# con-right.net
KiCad netlist of a schematic drawn in Altium Designer
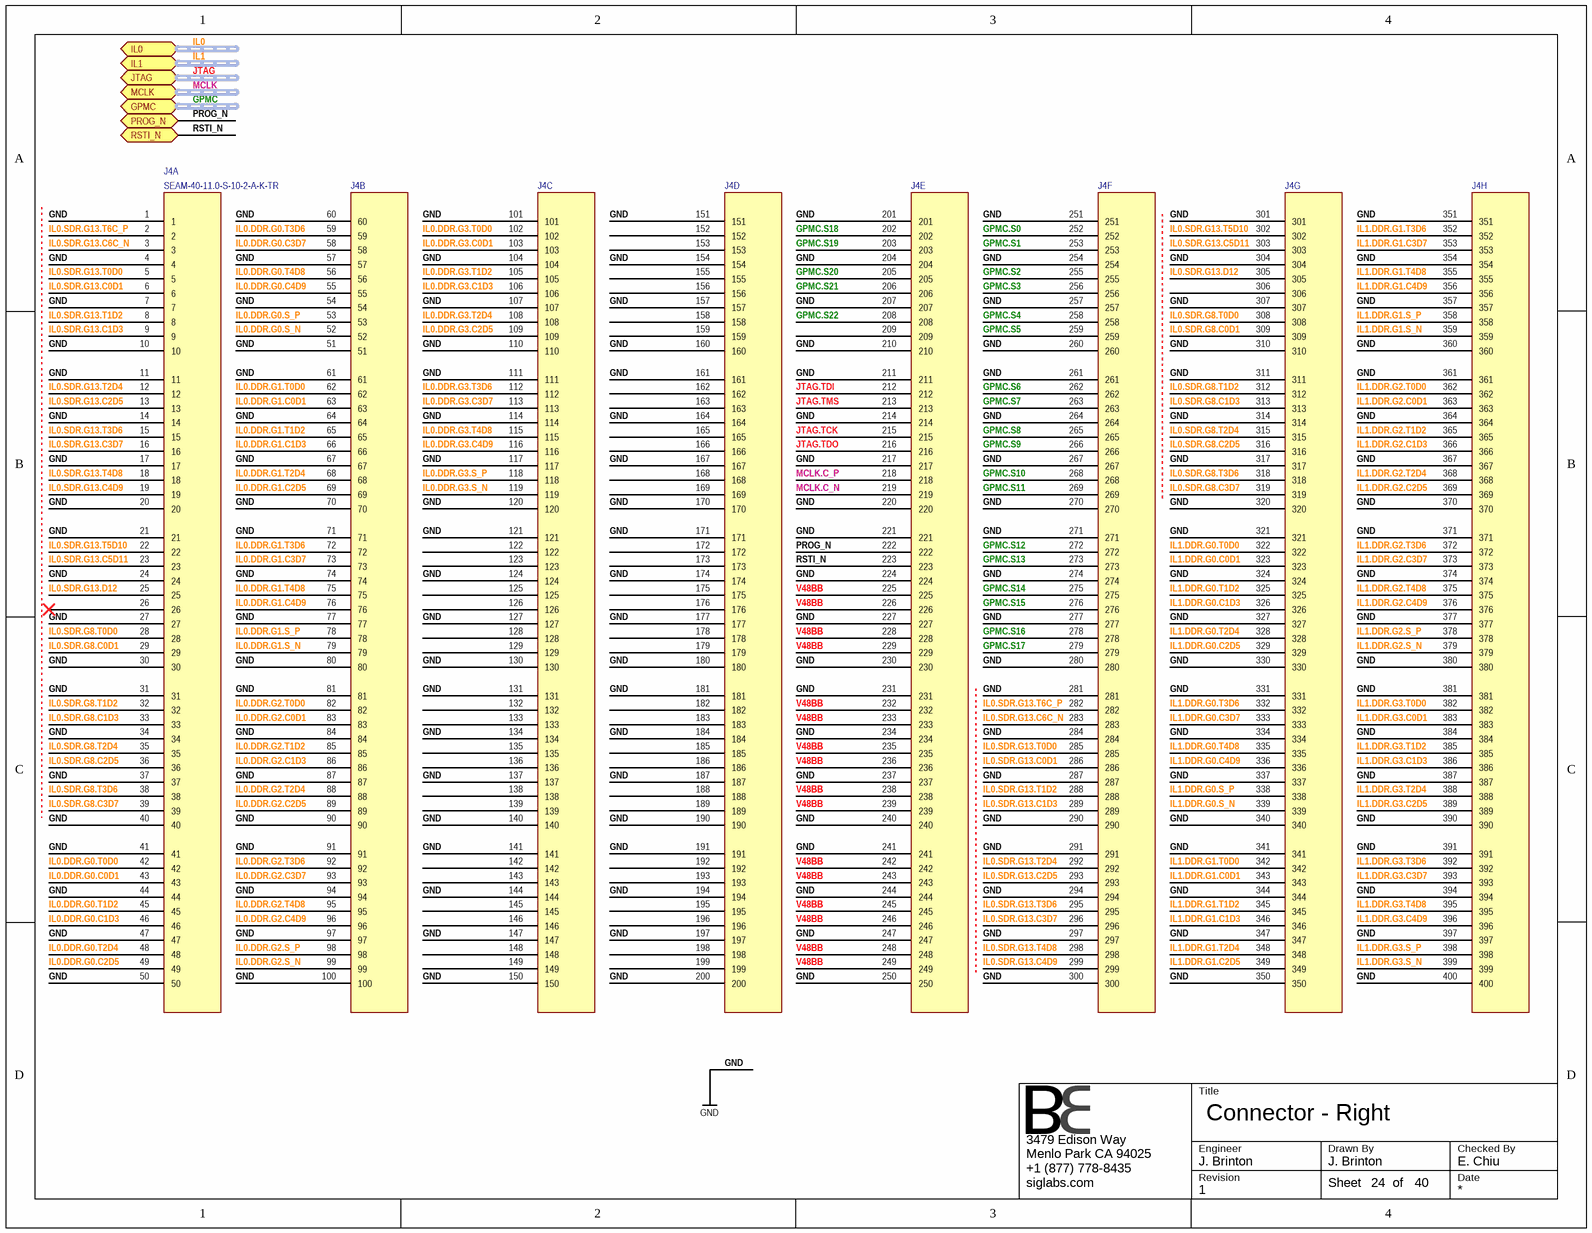
[diagram p0: con-right.SchDoc]

(export (version "E")
  (design (tool "Eeschema 10.0.6"))
  (components
    (comp (ref "J4")
      (value "SEAM-40-11.0-S-10-2-A-K-TR")
      (footprint "samtec:SEAM-40-11.0-S-10-2-A-K-TR")
      (description "Terminal Array Assembly, Surface Mount, 0.050\" Pitch, 400 Pins")
      (fields (field (name "MANUFACTURER") "Samtec"))
      (libsource (lib "samtec") (part "SEAM-40-11.0-S-10-2-A-K-TR"))
    )
  )
  (nets
    (net (code "6") (name "/GPMC.S0") (class "Default")
      (node (ref "J4") (pin "252") (pinfunction "252_252") (pintype "passive"))
    )
    (net (code "7") (name "/GPMC.S1") (class "Default")
      (node (ref "J4") (pin "253") (pinfunction "253_253") (pintype "passive"))
    )
    (net (code "8") (name "/GPMC.S2") (class "Default")
      (node (ref "J4") (pin "255") (pinfunction "255_255") (pintype "passive"))
    )
    (net (code "9") (name "/GPMC.S3") (class "Default")
      (node (ref "J4") (pin "256") (pinfunction "256_256") (pintype "passive"))
    )
    (net (code "10") (name "/GPMC.S4") (class "Default")
      (node (ref "J4") (pin "258") (pinfunction "258_258") (pintype "passive"))
    )
    (net (code "11") (name "/GPMC.S5") (class "Default")
      (node (ref "J4") (pin "259") (pinfunction "259_259") (pintype "passive"))
    )
    (net (code "12") (name "/GPMC.S6") (class "Default")
      (node (ref "J4") (pin "262") (pinfunction "262_262") (pintype "passive"))
    )
    (net (code "13") (name "/GPMC.S7") (class "Default")
      (node (ref "J4") (pin "263") (pinfunction "263_263") (pintype "passive"))
    )
    (net (code "14") (name "/GPMC.S8") (class "Default")
      (node (ref "J4") (pin "265") (pinfunction "265_265") (pintype "passive"))
    )
    (net (code "15") (name "/GPMC.S9") (class "Default")
      (node (ref "J4") (pin "266") (pinfunction "266_266") (pintype "passive"))
    )
    (net (code "16") (name "/GPMC.S10") (class "Default")
      (node (ref "J4") (pin "268") (pinfunction "268_268") (pintype "passive"))
    )
    (net (code "17") (name "/GPMC.S11") (class "Default")
      (node (ref "J4") (pin "269") (pinfunction "269_269") (pintype "passive"))
    )
    (net (code "18") (name "/GPMC.S12") (class "Default")
      (node (ref "J4") (pin "272") (pinfunction "272_272") (pintype "passive"))
    )
    (net (code "19") (name "/GPMC.S13") (class "Default")
      (node (ref "J4") (pin "273") (pinfunction "273_273") (pintype "passive"))
    )
    (net (code "20") (name "/GPMC.S14") (class "Default")
      (node (ref "J4") (pin "275") (pinfunction "275_275") (pintype "passive"))
    )
    (net (code "21") (name "/GPMC.S15") (class "Default")
      (node (ref "J4") (pin "276") (pinfunction "276_276") (pintype "passive"))
    )
    (net (code "22") (name "/GPMC.S16") (class "Default")
      (node (ref "J4") (pin "278") (pinfunction "278_278") (pintype "passive"))
    )
    (net (code "23") (name "/GPMC.S17") (class "Default")
      (node (ref "J4") (pin "279") (pinfunction "279_279") (pintype "passive"))
    )
    (net (code "24") (name "/GPMC.S18") (class "Default")
      (node (ref "J4") (pin "202") (pinfunction "202_202") (pintype "passive"))
    )
    (net (code "25") (name "/GPMC.S19") (class "Default")
      (node (ref "J4") (pin "203") (pinfunction "203_203") (pintype "passive"))
    )
    (net (code "26") (name "/GPMC.S20") (class "Default")
      (node (ref "J4") (pin "205") (pinfunction "205_205") (pintype "passive"))
    )
    (net (code "27") (name "/GPMC.S21") (class "Default")
      (node (ref "J4") (pin "206") (pinfunction "206_206") (pintype "passive"))
    )
    (net (code "28") (name "/GPMC.S22") (class "Default")
      (node (ref "J4") (pin "208") (pinfunction "208_208") (pintype "passive"))
    )
    (net (code "29") (name "/IL0.DDR.G0.C0D1") (class "Default")
      (node (ref "J4") (pin "43") (pinfunction "43_43") (pintype "passive"))
    )
    (net (code "30") (name "/IL0.DDR.G0.C1D3") (class "Default")
      (node (ref "J4") (pin "46") (pinfunction "46_46") (pintype "passive"))
    )
    (net (code "31") (name "/IL0.DDR.G0.C2D5") (class "Default")
      (node (ref "J4") (pin "49") (pinfunction "49_49") (pintype "passive"))
    )
    (net (code "32") (name "/IL0.DDR.G0.C3D7") (class "Default")
      (node (ref "J4") (pin "58") (pinfunction "58_58") (pintype "passive"))
    )
    (net (code "33") (name "/IL0.DDR.G0.C4D9") (class "Default")
      (node (ref "J4") (pin "55") (pinfunction "55_55") (pintype "passive"))
    )
    (net (code "34") (name "/IL0.DDR.G0.S_N") (class "Default")
      (node (ref "J4") (pin "52") (pinfunction "52_52") (pintype "passive"))
    )
    (net (code "35") (name "/IL0.DDR.G0.S_P") (class "Default")
      (node (ref "J4") (pin "53") (pinfunction "53_53") (pintype "passive"))
    )
    (net (code "36") (name "/IL0.DDR.G0.T0D0") (class "Default")
      (node (ref "J4") (pin "42") (pinfunction "42_42") (pintype "passive"))
    )
    (net (code "37") (name "/IL0.DDR.G0.T1D2") (class "Default")
      (node (ref "J4") (pin "45") (pinfunction "45_45") (pintype "passive"))
    )
    (net (code "38") (name "/IL0.DDR.G0.T2D4") (class "Default")
      (node (ref "J4") (pin "48") (pinfunction "48_48") (pintype "passive"))
    )
    (net (code "39") (name "/IL0.DDR.G0.T3D6") (class "Default")
      (node (ref "J4") (pin "59") (pinfunction "59_59") (pintype "passive"))
    )
    (net (code "40") (name "/IL0.DDR.G0.T4D8") (class "Default")
      (node (ref "J4") (pin "56") (pinfunction "56_56") (pintype "passive"))
    )
    (net (code "41") (name "/IL0.DDR.G1.C0D1") (class "Default")
      (node (ref "J4") (pin "63") (pinfunction "63_63") (pintype "passive"))
    )
    (net (code "42") (name "/IL0.DDR.G1.C1D3") (class "Default")
      (node (ref "J4") (pin "66") (pinfunction "66_66") (pintype "passive"))
    )
    (net (code "43") (name "/IL0.DDR.G1.C2D5") (class "Default")
      (node (ref "J4") (pin "69") (pinfunction "69_69") (pintype "passive"))
    )
    (net (code "44") (name "/IL0.DDR.G1.C3D7") (class "Default")
      (node (ref "J4") (pin "73") (pinfunction "73_73") (pintype "passive"))
    )
    (net (code "45") (name "/IL0.DDR.G1.C4D9") (class "Default")
      (node (ref "J4") (pin "76") (pinfunction "76_76") (pintype "passive"))
    )
    (net (code "46") (name "/IL0.DDR.G1.S_N") (class "Default")
      (node (ref "J4") (pin "79") (pinfunction "79_79") (pintype "passive"))
    )
    (net (code "47") (name "/IL0.DDR.G1.S_P") (class "Default")
      (node (ref "J4") (pin "78") (pinfunction "78_78") (pintype "passive"))
    )
    (net (code "48") (name "/IL0.DDR.G1.T0D0") (class "Default")
      (node (ref "J4") (pin "62") (pinfunction "62_62") (pintype "passive"))
    )
    (net (code "49") (name "/IL0.DDR.G1.T1D2") (class "Default")
      (node (ref "J4") (pin "65") (pinfunction "65_65") (pintype "passive"))
    )
    (net (code "50") (name "/IL0.DDR.G1.T2D4") (class "Default")
      (node (ref "J4") (pin "68") (pinfunction "68_68") (pintype "passive"))
    )
    (net (code "51") (name "/IL0.DDR.G1.T3D6") (class "Default")
      (node (ref "J4") (pin "72") (pinfunction "72_72") (pintype "passive"))
    )
    (net (code "52") (name "/IL0.DDR.G1.T4D8") (class "Default")
      (node (ref "J4") (pin "75") (pinfunction "75_75") (pintype "passive"))
    )
    (net (code "53") (name "/IL0.DDR.G2.C0D1") (class "Default")
      (node (ref "J4") (pin "83") (pinfunction "83_83") (pintype "passive"))
    )
    (net (code "54") (name "/IL0.DDR.G2.C1D3") (class "Default")
      (node (ref "J4") (pin "86") (pinfunction "86_86") (pintype "passive"))
    )
    (net (code "55") (name "/IL0.DDR.G2.C2D5") (class "Default")
      (node (ref "J4") (pin "89") (pinfunction "89_89") (pintype "passive"))
    )
    (net (code "56") (name "/IL0.DDR.G2.C3D7") (class "Default")
      (node (ref "J4") (pin "93") (pinfunction "93_93") (pintype "passive"))
    )
    (net (code "57") (name "/IL0.DDR.G2.C4D9") (class "Default")
      (node (ref "J4") (pin "96") (pinfunction "96_96") (pintype "passive"))
    )
    (net (code "58") (name "/IL0.DDR.G2.S_N") (class "Default")
      (node (ref "J4") (pin "99") (pinfunction "99_99") (pintype "passive"))
    )
    (net (code "59") (name "/IL0.DDR.G2.S_P") (class "Default")
      (node (ref "J4") (pin "98") (pinfunction "98_98") (pintype "passive"))
    )
    (net (code "60") (name "/IL0.DDR.G2.T0D0") (class "Default")
      (node (ref "J4") (pin "82") (pinfunction "82_82") (pintype "passive"))
    )
    (net (code "61") (name "/IL0.DDR.G2.T1D2") (class "Default")
      (node (ref "J4") (pin "85") (pinfunction "85_85") (pintype "passive"))
    )
    (net (code "62") (name "/IL0.DDR.G2.T2D4") (class "Default")
      (node (ref "J4") (pin "88") (pinfunction "88_88") (pintype "passive"))
    )
    (net (code "63") (name "/IL0.DDR.G2.T3D6") (class "Default")
      (node (ref "J4") (pin "92") (pinfunction "92_92") (pintype "passive"))
    )
    (net (code "64") (name "/IL0.DDR.G2.T4D8") (class "Default")
      (node (ref "J4") (pin "95") (pinfunction "95_95") (pintype "passive"))
    )
    (net (code "65") (name "/IL0.DDR.G3.C0D1") (class "Default")
      (node (ref "J4") (pin "103") (pinfunction "103_103") (pintype "passive"))
    )
    (net (code "66") (name "/IL0.DDR.G3.C1D3") (class "Default")
      (node (ref "J4") (pin "106") (pinfunction "106_106") (pintype "passive"))
    )
    (net (code "67") (name "/IL0.DDR.G3.C2D5") (class "Default")
      (node (ref "J4") (pin "109") (pinfunction "109_109") (pintype "passive"))
    )
    (net (code "68") (name "/IL0.DDR.G3.C3D7") (class "Default")
      (node (ref "J4") (pin "113") (pinfunction "113_113") (pintype "passive"))
    )
    (net (code "69") (name "/IL0.DDR.G3.C4D9") (class "Default")
      (node (ref "J4") (pin "116") (pinfunction "116_116") (pintype "passive"))
    )
    (net (code "70") (name "/IL0.DDR.G3.S_N") (class "Default")
      (node (ref "J4") (pin "119") (pinfunction "119_119") (pintype "passive"))
    )
    (net (code "71") (name "/IL0.DDR.G3.S_P") (class "Default")
      (node (ref "J4") (pin "118") (pinfunction "118_118") (pintype "passive"))
    )
    (net (code "72") (name "/IL0.DDR.G3.T0D0") (class "Default")
      (node (ref "J4") (pin "102") (pinfunction "102_102") (pintype "passive"))
    )
    (net (code "73") (name "/IL0.DDR.G3.T1D2") (class "Default")
      (node (ref "J4") (pin "105") (pinfunction "105_105") (pintype "passive"))
    )
    (net (code "74") (name "/IL0.DDR.G3.T2D4") (class "Default")
      (node (ref "J4") (pin "108") (pinfunction "108_108") (pintype "passive"))
    )
    (net (code "75") (name "/IL0.DDR.G3.T3D6") (class "Default")
      (node (ref "J4") (pin "112") (pinfunction "112_112") (pintype "passive"))
    )
    (net (code "76") (name "/IL0.DDR.G3.T4D8") (class "Default")
      (node (ref "J4") (pin "115") (pinfunction "115_115") (pintype "passive"))
    )
    (net (code "77") (name "/IL0.SDR.G8.C0D1") (class "Default")
      (node (ref "J4") (pin "29") (pinfunction "29_29") (pintype "passive"))
      (node (ref "J4") (pin "309") (pinfunction "309_309") (pintype "passive"))
    )
    (net (code "78") (name "/IL0.SDR.G8.C1D3") (class "Default")
      (node (ref "J4") (pin "313") (pinfunction "313_313") (pintype "passive"))
      (node (ref "J4") (pin "33") (pinfunction "33_33") (pintype "passive"))
    )
    (net (code "79") (name "/IL0.SDR.G8.C2D5") (class "Default")
      (node (ref "J4") (pin "316") (pinfunction "316_316") (pintype "passive"))
      (node (ref "J4") (pin "36") (pinfunction "36_36") (pintype "passive"))
    )
    (net (code "80") (name "/IL0.SDR.G8.C3D7") (class "Default")
      (node (ref "J4") (pin "319") (pinfunction "319_319") (pintype "passive"))
      (node (ref "J4") (pin "39") (pinfunction "39_39") (pintype "passive"))
    )
    (net (code "81") (name "/IL0.SDR.G8.T0D0") (class "Default")
      (node (ref "J4") (pin "28") (pinfunction "28_28") (pintype "passive"))
      (node (ref "J4") (pin "308") (pinfunction "308_308") (pintype "passive"))
    )
    (net (code "82") (name "/IL0.SDR.G8.T1D2") (class "Default")
      (node (ref "J4") (pin "312") (pinfunction "312_312") (pintype "passive"))
      (node (ref "J4") (pin "32") (pinfunction "32_32") (pintype "passive"))
    )
    (net (code "83") (name "/IL0.SDR.G8.T2D4") (class "Default")
      (node (ref "J4") (pin "315") (pinfunction "315_315") (pintype "passive"))
      (node (ref "J4") (pin "35") (pinfunction "35_35") (pintype "passive"))
    )
    (net (code "84") (name "/IL0.SDR.G8.T3D6") (class "Default")
      (node (ref "J4") (pin "318") (pinfunction "318_318") (pintype "passive"))
      (node (ref "J4") (pin "38") (pinfunction "38_38") (pintype "passive"))
    )
    (net (code "85") (name "/IL0.SDR.G13.C0D1") (class "Default")
      (node (ref "J4") (pin "286") (pinfunction "286_286") (pintype "passive"))
      (node (ref "J4") (pin "6") (pinfunction "6_6") (pintype "passive"))
    )
    (net (code "86") (name "/IL0.SDR.G13.C1D3") (class "Default")
      (node (ref "J4") (pin "289") (pinfunction "289_289") (pintype "passive"))
      (node (ref "J4") (pin "9") (pinfunction "9_9") (pintype "passive"))
    )
    (net (code "87") (name "/IL0.SDR.G13.C2D5") (class "Default")
      (node (ref "J4") (pin "13") (pinfunction "13_13") (pintype "passive"))
      (node (ref "J4") (pin "293") (pinfunction "293_293") (pintype "passive"))
    )
    (net (code "88") (name "/IL0.SDR.G13.C3D7") (class "Default")
      (node (ref "J4") (pin "16") (pinfunction "16_16") (pintype "passive"))
      (node (ref "J4") (pin "296") (pinfunction "296_296") (pintype "passive"))
    )
    (net (code "89") (name "/IL0.SDR.G13.C4D9") (class "Default")
      (node (ref "J4") (pin "19") (pinfunction "19_19") (pintype "passive"))
      (node (ref "J4") (pin "299") (pinfunction "299_299") (pintype "passive"))
    )
    (net (code "90") (name "/IL0.SDR.G13.C5D11") (class "Default")
      (node (ref "J4") (pin "23") (pinfunction "23_23") (pintype "passive"))
      (node (ref "J4") (pin "303") (pinfunction "303_303") (pintype "passive"))
    )
    (net (code "91") (name "/IL0.SDR.G13.C6C_N") (class "Default")
      (node (ref "J4") (pin "283") (pinfunction "283_283") (pintype "passive"))
      (node (ref "J4") (pin "3") (pinfunction "3_3") (pintype "passive"))
    )
    (net (code "92") (name "/IL0.SDR.G13.D12") (class "Default")
      (node (ref "J4") (pin "25") (pinfunction "25_25") (pintype "passive"))
      (node (ref "J4") (pin "305") (pinfunction "305_305") (pintype "passive"))
    )
    (net (code "93") (name "/IL0.SDR.G13.T0D0") (class "Default")
      (node (ref "J4") (pin "285") (pinfunction "285_285") (pintype "passive"))
      (node (ref "J4") (pin "5") (pinfunction "5_5") (pintype "passive"))
    )
    (net (code "94") (name "/IL0.SDR.G13.T1D2") (class "Default")
      (node (ref "J4") (pin "288") (pinfunction "288_288") (pintype "passive"))
      (node (ref "J4") (pin "8") (pinfunction "8_8") (pintype "passive"))
    )
    (net (code "95") (name "/IL0.SDR.G13.T2D4") (class "Default")
      (node (ref "J4") (pin "12") (pinfunction "12_12") (pintype "passive"))
      (node (ref "J4") (pin "292") (pinfunction "292_292") (pintype "passive"))
    )
    (net (code "96") (name "/IL0.SDR.G13.T3D6") (class "Default")
      (node (ref "J4") (pin "15") (pinfunction "15_15") (pintype "passive"))
      (node (ref "J4") (pin "295") (pinfunction "295_295") (pintype "passive"))
    )
    (net (code "97") (name "/IL0.SDR.G13.T4D8") (class "Default")
      (node (ref "J4") (pin "18") (pinfunction "18_18") (pintype "passive"))
      (node (ref "J4") (pin "298") (pinfunction "298_298") (pintype "passive"))
    )
    (net (code "98") (name "/IL0.SDR.G13.T5D10") (class "Default")
      (node (ref "J4") (pin "22") (pinfunction "22_22") (pintype "passive"))
      (node (ref "J4") (pin "302") (pinfunction "302_302") (pintype "passive"))
    )
    (net (code "99") (name "/IL0.SDR.G13.T6C_P") (class "Default")
      (node (ref "J4") (pin "2") (pinfunction "2_2") (pintype "passive"))
      (node (ref "J4") (pin "282") (pinfunction "282_282") (pintype "passive"))
    )
    (net (code "100") (name "/IL1.DDR.G0.C0D1") (class "Default")
      (node (ref "J4") (pin "323") (pinfunction "323_323") (pintype "passive"))
    )
    (net (code "101") (name "/IL1.DDR.G0.C1D3") (class "Default")
      (node (ref "J4") (pin "326") (pinfunction "326_326") (pintype "passive"))
    )
    (net (code "102") (name "/IL1.DDR.G0.C2D5") (class "Default")
      (node (ref "J4") (pin "329") (pinfunction "329_329") (pintype "passive"))
    )
    (net (code "103") (name "/IL1.DDR.G0.C3D7") (class "Default")
      (node (ref "J4") (pin "333") (pinfunction "333_333") (pintype "passive"))
    )
    (net (code "104") (name "/IL1.DDR.G0.C4D9") (class "Default")
      (node (ref "J4") (pin "336") (pinfunction "336_336") (pintype "passive"))
    )
    (net (code "105") (name "/IL1.DDR.G0.S_N") (class "Default")
      (node (ref "J4") (pin "339") (pinfunction "339_339") (pintype "passive"))
    )
    (net (code "106") (name "/IL1.DDR.G0.S_P") (class "Default")
      (node (ref "J4") (pin "338") (pinfunction "338_338") (pintype "passive"))
    )
    (net (code "107") (name "/IL1.DDR.G0.T0D0") (class "Default")
      (node (ref "J4") (pin "322") (pinfunction "322_322") (pintype "passive"))
    )
    (net (code "108") (name "/IL1.DDR.G0.T1D2") (class "Default")
      (node (ref "J4") (pin "325") (pinfunction "325_325") (pintype "passive"))
    )
    (net (code "109") (name "/IL1.DDR.G0.T2D4") (class "Default")
      (node (ref "J4") (pin "328") (pinfunction "328_328") (pintype "passive"))
    )
    (net (code "110") (name "/IL1.DDR.G0.T3D6") (class "Default")
      (node (ref "J4") (pin "332") (pinfunction "332_332") (pintype "passive"))
    )
    (net (code "111") (name "/IL1.DDR.G0.T4D8") (class "Default")
      (node (ref "J4") (pin "335") (pinfunction "335_335") (pintype "passive"))
    )
    (net (code "112") (name "/IL1.DDR.G1.C0D1") (class "Default")
      (node (ref "J4") (pin "343") (pinfunction "343_343") (pintype "passive"))
    )
    (net (code "113") (name "/IL1.DDR.G1.C1D3") (class "Default")
      (node (ref "J4") (pin "346") (pinfunction "346_346") (pintype "passive"))
    )
    (net (code "114") (name "/IL1.DDR.G1.C2D5") (class "Default")
      (node (ref "J4") (pin "349") (pinfunction "349_349") (pintype "passive"))
    )
    (net (code "115") (name "/IL1.DDR.G1.C3D7") (class "Default")
      (node (ref "J4") (pin "353") (pinfunction "353_353") (pintype "passive"))
    )
    (net (code "116") (name "/IL1.DDR.G1.C4D9") (class "Default")
      (node (ref "J4") (pin "356") (pinfunction "356_356") (pintype "passive"))
    )
    (net (code "117") (name "/IL1.DDR.G1.S_N") (class "Default")
      (node (ref "J4") (pin "359") (pinfunction "359_359") (pintype "passive"))
    )
    (net (code "118") (name "/IL1.DDR.G1.S_P") (class "Default")
      (node (ref "J4") (pin "358") (pinfunction "358_358") (pintype "passive"))
    )
    (net (code "119") (name "/IL1.DDR.G1.T0D0") (class "Default")
      (node (ref "J4") (pin "342") (pinfunction "342_342") (pintype "passive"))
    )
    (net (code "120") (name "/IL1.DDR.G1.T1D2") (class "Default")
      (node (ref "J4") (pin "345") (pinfunction "345_345") (pintype "passive"))
    )
    (net (code "121") (name "/IL1.DDR.G1.T2D4") (class "Default")
      (node (ref "J4") (pin "348") (pinfunction "348_348") (pintype "passive"))
    )
    (net (code "122") (name "/IL1.DDR.G1.T3D6") (class "Default")
      (node (ref "J4") (pin "352") (pinfunction "352_352") (pintype "passive"))
    )
    (net (code "123") (name "/IL1.DDR.G1.T4D8") (class "Default")
      (node (ref "J4") (pin "355") (pinfunction "355_355") (pintype "passive"))
    )
    (net (code "124") (name "/IL1.DDR.G2.C0D1") (class "Default")
      (node (ref "J4") (pin "363") (pinfunction "363_363") (pintype "passive"))
    )
    (net (code "125") (name "/IL1.DDR.G2.C1D3") (class "Default")
      (node (ref "J4") (pin "366") (pinfunction "366_366") (pintype "passive"))
    )
    (net (code "126") (name "/IL1.DDR.G2.C2D5") (class "Default")
      (node (ref "J4") (pin "369") (pinfunction "369_369") (pintype "passive"))
    )
    (net (code "127") (name "/IL1.DDR.G2.C3D7") (class "Default")
      (node (ref "J4") (pin "373") (pinfunction "373_373") (pintype "passive"))
    )
    (net (code "128") (name "/IL1.DDR.G2.C4D9") (class "Default")
      (node (ref "J4") (pin "376") (pinfunction "376_376") (pintype "passive"))
    )
    (net (code "129") (name "/IL1.DDR.G2.S_N") (class "Default")
      (node (ref "J4") (pin "379") (pinfunction "379_379") (pintype "passive"))
    )
    (net (code "130") (name "/IL1.DDR.G2.S_P") (class "Default")
      (node (ref "J4") (pin "378") (pinfunction "378_378") (pintype "passive"))
    )
    (net (code "131") (name "/IL1.DDR.G2.T0D0") (class "Default")
      (node (ref "J4") (pin "362") (pinfunction "362_362") (pintype "passive"))
    )
    (net (code "132") (name "/IL1.DDR.G2.T1D2") (class "Default")
      (node (ref "J4") (pin "365") (pinfunction "365_365") (pintype "passive"))
    )
    (net (code "133") (name "/IL1.DDR.G2.T2D4") (class "Default")
      (node (ref "J4") (pin "368") (pinfunction "368_368") (pintype "passive"))
    )
    (net (code "134") (name "/IL1.DDR.G2.T3D6") (class "Default")
      (node (ref "J4") (pin "372") (pinfunction "372_372") (pintype "passive"))
    )
    (net (code "135") (name "/IL1.DDR.G2.T4D8") (class "Default")
      (node (ref "J4") (pin "375") (pinfunction "375_375") (pintype "passive"))
    )
    (net (code "136") (name "/IL1.DDR.G3.C0D1") (class "Default")
      (node (ref "J4") (pin "383") (pinfunction "383_383") (pintype "passive"))
    )
    (net (code "137") (name "/IL1.DDR.G3.C1D3") (class "Default")
      (node (ref "J4") (pin "386") (pinfunction "386_386") (pintype "passive"))
    )
    (net (code "138") (name "/IL1.DDR.G3.C2D5") (class "Default")
      (node (ref "J4") (pin "389") (pinfunction "389_389") (pintype "passive"))
    )
    (net (code "139") (name "/IL1.DDR.G3.C3D7") (class "Default")
      (node (ref "J4") (pin "393") (pinfunction "393_393") (pintype "passive"))
    )
    (net (code "140") (name "/IL1.DDR.G3.C4D9") (class "Default")
      (node (ref "J4") (pin "396") (pinfunction "396_396") (pintype "passive"))
    )
    (net (code "141") (name "/IL1.DDR.G3.S_N") (class "Default")
      (node (ref "J4") (pin "399") (pinfunction "399_399") (pintype "passive"))
    )
    (net (code "142") (name "/IL1.DDR.G3.S_P") (class "Default")
      (node (ref "J4") (pin "398") (pinfunction "398_398") (pintype "passive"))
    )
    (net (code "143") (name "/IL1.DDR.G3.T0D0") (class "Default")
      (node (ref "J4") (pin "382") (pinfunction "382_382") (pintype "passive"))
    )
    (net (code "144") (name "/IL1.DDR.G3.T1D2") (class "Default")
      (node (ref "J4") (pin "385") (pinfunction "385_385") (pintype "passive"))
    )
    (net (code "145") (name "/IL1.DDR.G3.T2D4") (class "Default")
      (node (ref "J4") (pin "388") (pinfunction "388_388") (pintype "passive"))
    )
    (net (code "146") (name "/IL1.DDR.G3.T3D6") (class "Default")
      (node (ref "J4") (pin "392") (pinfunction "392_392") (pintype "passive"))
    )
    (net (code "147") (name "/IL1.DDR.G3.T4D8") (class "Default")
      (node (ref "J4") (pin "395") (pinfunction "395_395") (pintype "passive"))
    )
    (net (code "148") (name "/JTAG.TCK") (class "Default")
      (node (ref "J4") (pin "215") (pinfunction "215_215") (pintype "passive"))
    )
    (net (code "149") (name "/JTAG.TDI") (class "Default")
      (node (ref "J4") (pin "212") (pinfunction "212_212") (pintype "passive"))
    )
    (net (code "150") (name "/JTAG.TDO") (class "Default")
      (node (ref "J4") (pin "216") (pinfunction "216_216") (pintype "passive"))
    )
    (net (code "151") (name "/JTAG.TMS") (class "Default")
      (node (ref "J4") (pin "213") (pinfunction "213_213") (pintype "passive"))
    )
    (net (code "152") (name "/MCLK.C_N") (class "Default")
      (node (ref "J4") (pin "219") (pinfunction "219_219") (pintype "passive"))
    )
    (net (code "153") (name "/MCLK.C_P") (class "Default")
      (node (ref "J4") (pin "218") (pinfunction "218_218") (pintype "passive"))
    )
    (net (code "154") (name "/PROG_N") (class "Default")
      (node (ref "J4") (pin "222") (pinfunction "222_222") (pintype "passive"))
    )
    (net (code "155") (name "/RSTI_N") (class "Default")
      (node (ref "J4") (pin "223") (pinfunction "223_223") (pintype "passive"))
    )
    (net (code "156") (name "/V48BB") (class "Default")
      (node (ref "J4") (pin "225") (pinfunction "225_225") (pintype "passive"))
      (node (ref "J4") (pin "226") (pinfunction "226_226") (pintype "passive"))
      (node (ref "J4") (pin "228") (pinfunction "228_228") (pintype "passive"))
      (node (ref "J4") (pin "229") (pinfunction "229_229") (pintype "passive"))
      (node (ref "J4") (pin "232") (pinfunction "232_232") (pintype "passive"))
      (node (ref "J4") (pin "233") (pinfunction "233_233") (pintype "passive"))
      (node (ref "J4") (pin "235") (pinfunction "235_235") (pintype "passive"))
      (node (ref "J4") (pin "236") (pinfunction "236_236") (pintype "passive"))
      (node (ref "J4") (pin "238") (pinfunction "238_238") (pintype "passive"))
      (node (ref "J4") (pin "239") (pinfunction "239_239") (pintype "passive"))
      (node (ref "J4") (pin "242") (pinfunction "242_242") (pintype "passive"))
      (node (ref "J4") (pin "243") (pinfunction "243_243") (pintype "passive"))
      (node (ref "J4") (pin "245") (pinfunction "245_245") (pintype "passive"))
      (node (ref "J4") (pin "246") (pinfunction "246_246") (pintype "passive"))
      (node (ref "J4") (pin "248") (pinfunction "248_248") (pintype "passive"))
      (node (ref "J4") (pin "249") (pinfunction "249_249") (pintype "passive"))
    )
    (net (code "162") (name "GND") (class "Default")
      (node (ref "J4") (pin "1") (pinfunction "1_1") (pintype "passive"))
      (node (ref "J4") (pin "10") (pinfunction "10_10") (pintype "passive"))
      (node (ref "J4") (pin "100") (pinfunction "100_100") (pintype "passive"))
      (node (ref "J4") (pin "101") (pinfunction "101_101") (pintype "passive"))
      (node (ref "J4") (pin "104") (pinfunction "104_104") (pintype "passive"))
      (node (ref "J4") (pin "107") (pinfunction "107_107") (pintype "passive"))
      (node (ref "J4") (pin "11") (pinfunction "11_11") (pintype "passive"))
      (node (ref "J4") (pin "110") (pinfunction "110_110") (pintype "passive"))
      (node (ref "J4") (pin "111") (pinfunction "111_111") (pintype "passive"))
      (node (ref "J4") (pin "114") (pinfunction "114_114") (pintype "passive"))
      (node (ref "J4") (pin "117") (pinfunction "117_117") (pintype "passive"))
      (node (ref "J4") (pin "120") (pinfunction "120_120") (pintype "passive"))
      (node (ref "J4") (pin "121") (pinfunction "121_121") (pintype "passive"))
      (node (ref "J4") (pin "124") (pinfunction "124_124") (pintype "passive"))
      (node (ref "J4") (pin "127") (pinfunction "127_127") (pintype "passive"))
      (node (ref "J4") (pin "130") (pinfunction "130_130") (pintype "passive"))
      (node (ref "J4") (pin "131") (pinfunction "131_131") (pintype "passive"))
      (node (ref "J4") (pin "134") (pinfunction "134_134") (pintype "passive"))
      (node (ref "J4") (pin "137") (pinfunction "137_137") (pintype "passive"))
      (node (ref "J4") (pin "14") (pinfunction "14_14") (pintype "passive"))
      (node (ref "J4") (pin "140") (pinfunction "140_140") (pintype "passive"))
      (node (ref "J4") (pin "141") (pinfunction "141_141") (pintype "passive"))
      (node (ref "J4") (pin "144") (pinfunction "144_144") (pintype "passive"))
      (node (ref "J4") (pin "147") (pinfunction "147_147") (pintype "passive"))
      (node (ref "J4") (pin "150") (pinfunction "150_150") (pintype "passive"))
      (node (ref "J4") (pin "151") (pinfunction "151_151") (pintype "passive"))
      (node (ref "J4") (pin "154") (pinfunction "154_154") (pintype "passive"))
      (node (ref "J4") (pin "157") (pinfunction "157_157") (pintype "passive"))
      (node (ref "J4") (pin "160") (pinfunction "160_160") (pintype "passive"))
      (node (ref "J4") (pin "161") (pinfunction "161_161") (pintype "passive"))
      (node (ref "J4") (pin "164") (pinfunction "164_164") (pintype "passive"))
      (node (ref "J4") (pin "167") (pinfunction "167_167") (pintype "passive"))
      (node (ref "J4") (pin "17") (pinfunction "17_17") (pintype "passive"))
      (node (ref "J4") (pin "170") (pinfunction "170_170") (pintype "passive"))
      (node (ref "J4") (pin "171") (pinfunction "171_171") (pintype "passive"))
      (node (ref "J4") (pin "174") (pinfunction "174_174") (pintype "passive"))
      (node (ref "J4") (pin "177") (pinfunction "177_177") (pintype "passive"))
      (node (ref "J4") (pin "180") (pinfunction "180_180") (pintype "passive"))
      (node (ref "J4") (pin "181") (pinfunction "181_181") (pintype "passive"))
      (node (ref "J4") (pin "184") (pinfunction "184_184") (pintype "passive"))
      (node (ref "J4") (pin "187") (pinfunction "187_187") (pintype "passive"))
      (node (ref "J4") (pin "190") (pinfunction "190_190") (pintype "passive"))
      (node (ref "J4") (pin "191") (pinfunction "191_191") (pintype "passive"))
      (node (ref "J4") (pin "194") (pinfunction "194_194") (pintype "passive"))
      (node (ref "J4") (pin "197") (pinfunction "197_197") (pintype "passive"))
      (node (ref "J4") (pin "20") (pinfunction "20_20") (pintype "passive"))
      (node (ref "J4") (pin "200") (pinfunction "200_200") (pintype "passive"))
      (node (ref "J4") (pin "201") (pinfunction "201_201") (pintype "passive"))
      (node (ref "J4") (pin "204") (pinfunction "204_204") (pintype "passive"))
      (node (ref "J4") (pin "207") (pinfunction "207_207") (pintype "passive"))
      (node (ref "J4") (pin "21") (pinfunction "21_21") (pintype "passive"))
      (node (ref "J4") (pin "210") (pinfunction "210_210") (pintype "passive"))
      (node (ref "J4") (pin "211") (pinfunction "211_211") (pintype "passive"))
      (node (ref "J4") (pin "214") (pinfunction "214_214") (pintype "passive"))
      (node (ref "J4") (pin "217") (pinfunction "217_217") (pintype "passive"))
      (node (ref "J4") (pin "220") (pinfunction "220_220") (pintype "passive"))
      (node (ref "J4") (pin "221") (pinfunction "221_221") (pintype "passive"))
      (node (ref "J4") (pin "224") (pinfunction "224_224") (pintype "passive"))
      (node (ref "J4") (pin "227") (pinfunction "227_227") (pintype "passive"))
      (node (ref "J4") (pin "230") (pinfunction "230_230") (pintype "passive"))
      (node (ref "J4") (pin "231") (pinfunction "231_231") (pintype "passive"))
      (node (ref "J4") (pin "234") (pinfunction "234_234") (pintype "passive"))
      (node (ref "J4") (pin "237") (pinfunction "237_237") (pintype "passive"))
      (node (ref "J4") (pin "24") (pinfunction "24_24") (pintype "passive"))
      (node (ref "J4") (pin "240") (pinfunction "240_240") (pintype "passive"))
      (node (ref "J4") (pin "241") (pinfunction "241_241") (pintype "passive"))
      (node (ref "J4") (pin "244") (pinfunction "244_244") (pintype "passive"))
      (node (ref "J4") (pin "247") (pinfunction "247_247") (pintype "passive"))
      (node (ref "J4") (pin "250") (pinfunction "250_250") (pintype "passive"))
      (node (ref "J4") (pin "251") (pinfunction "251_251") (pintype "passive"))
      (node (ref "J4") (pin "254") (pinfunction "254_254") (pintype "passive"))
      (node (ref "J4") (pin "257") (pinfunction "257_257") (pintype "passive"))
      (node (ref "J4") (pin "260") (pinfunction "260_260") (pintype "passive"))
      (node (ref "J4") (pin "261") (pinfunction "261_261") (pintype "passive"))
      (node (ref "J4") (pin "264") (pinfunction "264_264") (pintype "passive"))
      (node (ref "J4") (pin "267") (pinfunction "267_267") (pintype "passive"))
      (node (ref "J4") (pin "27") (pinfunction "27_27") (pintype "passive"))
      (node (ref "J4") (pin "270") (pinfunction "270_270") (pintype "passive"))
      (node (ref "J4") (pin "271") (pinfunction "271_271") (pintype "passive"))
      (node (ref "J4") (pin "274") (pinfunction "274_274") (pintype "passive"))
      (node (ref "J4") (pin "277") (pinfunction "277_277") (pintype "passive"))
      (node (ref "J4") (pin "280") (pinfunction "280_280") (pintype "passive"))
      (node (ref "J4") (pin "281") (pinfunction "281_281") (pintype "passive"))
      (node (ref "J4") (pin "284") (pinfunction "284_284") (pintype "passive"))
      (node (ref "J4") (pin "287") (pinfunction "287_287") (pintype "passive"))
      (node (ref "J4") (pin "290") (pinfunction "290_290") (pintype "passive"))
      (node (ref "J4") (pin "291") (pinfunction "291_291") (pintype "passive"))
      (node (ref "J4") (pin "294") (pinfunction "294_294") (pintype "passive"))
      (node (ref "J4") (pin "297") (pinfunction "297_297") (pintype "passive"))
      (node (ref "J4") (pin "30") (pinfunction "30_30") (pintype "passive"))
      (node (ref "J4") (pin "300") (pinfunction "300_300") (pintype "passive"))
      (node (ref "J4") (pin "301") (pinfunction "301_301") (pintype "passive"))
      (node (ref "J4") (pin "304") (pinfunction "304_304") (pintype "passive"))
      (node (ref "J4") (pin "307") (pinfunction "307_307") (pintype "passive"))
      (node (ref "J4") (pin "31") (pinfunction "31_31") (pintype "passive"))
      (node (ref "J4") (pin "310") (pinfunction "310_310") (pintype "passive"))
      (node (ref "J4") (pin "311") (pinfunction "311_311") (pintype "passive"))
      (node (ref "J4") (pin "314") (pinfunction "314_314") (pintype "passive"))
      (node (ref "J4") (pin "317") (pinfunction "317_317") (pintype "passive"))
      (node (ref "J4") (pin "320") (pinfunction "320_320") (pintype "passive"))
      (node (ref "J4") (pin "321") (pinfunction "321_321") (pintype "passive"))
      (node (ref "J4") (pin "324") (pinfunction "324_324") (pintype "passive"))
      (node (ref "J4") (pin "327") (pinfunction "327_327") (pintype "passive"))
      (node (ref "J4") (pin "330") (pinfunction "330_330") (pintype "passive"))
      (node (ref "J4") (pin "331") (pinfunction "331_331") (pintype "passive"))
      (node (ref "J4") (pin "334") (pinfunction "334_334") (pintype "passive"))
      (node (ref "J4") (pin "337") (pinfunction "337_337") (pintype "passive"))
      (node (ref "J4") (pin "34") (pinfunction "34_34") (pintype "passive"))
      (node (ref "J4") (pin "340") (pinfunction "340_340") (pintype "passive"))
      (node (ref "J4") (pin "341") (pinfunction "341_341") (pintype "passive"))
      (node (ref "J4") (pin "344") (pinfunction "344_344") (pintype "passive"))
      (node (ref "J4") (pin "347") (pinfunction "347_347") (pintype "passive"))
      (node (ref "J4") (pin "350") (pinfunction "350_350") (pintype "passive"))
      (node (ref "J4") (pin "351") (pinfunction "351_351") (pintype "passive"))
      (node (ref "J4") (pin "354") (pinfunction "354_354") (pintype "passive"))
      (node (ref "J4") (pin "357") (pinfunction "357_357") (pintype "passive"))
      (node (ref "J4") (pin "360") (pinfunction "360_360") (pintype "passive"))
      (node (ref "J4") (pin "361") (pinfunction "361_361") (pintype "passive"))
      (node (ref "J4") (pin "364") (pinfunction "364_364") (pintype "passive"))
      (node (ref "J4") (pin "367") (pinfunction "367_367") (pintype "passive"))
      (node (ref "J4") (pin "37") (pinfunction "37_37") (pintype "passive"))
      (node (ref "J4") (pin "370") (pinfunction "370_370") (pintype "passive"))
      (node (ref "J4") (pin "371") (pinfunction "371_371") (pintype "passive"))
      (node (ref "J4") (pin "374") (pinfunction "374_374") (pintype "passive"))
      (node (ref "J4") (pin "377") (pinfunction "377_377") (pintype "passive"))
      (node (ref "J4") (pin "380") (pinfunction "380_380") (pintype "passive"))
      (node (ref "J4") (pin "381") (pinfunction "381_381") (pintype "passive"))
      (node (ref "J4") (pin "384") (pinfunction "384_384") (pintype "passive"))
      (node (ref "J4") (pin "387") (pinfunction "387_387") (pintype "passive"))
      (node (ref "J4") (pin "390") (pinfunction "390_390") (pintype "passive"))
      (node (ref "J4") (pin "391") (pinfunction "391_391") (pintype "passive"))
      (node (ref "J4") (pin "394") (pinfunction "394_394") (pintype "passive"))
      (node (ref "J4") (pin "397") (pinfunction "397_397") (pintype "passive"))
      (node (ref "J4") (pin "4") (pinfunction "4_4") (pintype "passive"))
      (node (ref "J4") (pin "40") (pinfunction "40_40") (pintype "passive"))
      (node (ref "J4") (pin "400") (pinfunction "400_400") (pintype "passive"))
      (node (ref "J4") (pin "41") (pinfunction "41_41") (pintype "passive"))
      (node (ref "J4") (pin "44") (pinfunction "44_44") (pintype "passive"))
      (node (ref "J4") (pin "47") (pinfunction "47_47") (pintype "passive"))
      (node (ref "J4") (pin "50") (pinfunction "50_50") (pintype "passive"))
      (node (ref "J4") (pin "51") (pinfunction "51_51") (pintype "passive"))
      (node (ref "J4") (pin "54") (pinfunction "54_54") (pintype "passive"))
      (node (ref "J4") (pin "57") (pinfunction "57_57") (pintype "passive"))
      (node (ref "J4") (pin "60") (pinfunction "60_60") (pintype "passive"))
      (node (ref "J4") (pin "61") (pinfunction "61_61") (pintype "passive"))
      (node (ref "J4") (pin "64") (pinfunction "64_64") (pintype "passive"))
      (node (ref "J4") (pin "67") (pinfunction "67_67") (pintype "passive"))
      (node (ref "J4") (pin "7") (pinfunction "7_7") (pintype "passive"))
      (node (ref "J4") (pin "70") (pinfunction "70_70") (pintype "passive"))
      (node (ref "J4") (pin "71") (pinfunction "71_71") (pintype "passive"))
      (node (ref "J4") (pin "74") (pinfunction "74_74") (pintype "passive"))
      (node (ref "J4") (pin "77") (pinfunction "77_77") (pintype "passive"))
      (node (ref "J4") (pin "80") (pinfunction "80_80") (pintype "passive"))
      (node (ref "J4") (pin "81") (pinfunction "81_81") (pintype "passive"))
      (node (ref "J4") (pin "84") (pinfunction "84_84") (pintype "passive"))
      (node (ref "J4") (pin "87") (pinfunction "87_87") (pintype "passive"))
      (node (ref "J4") (pin "90") (pinfunction "90_90") (pintype "passive"))
      (node (ref "J4") (pin "91") (pinfunction "91_91") (pintype "passive"))
      (node (ref "J4") (pin "94") (pinfunction "94_94") (pintype "passive"))
      (node (ref "J4") (pin "97") (pinfunction "97_97") (pintype "passive"))
    )
    (net (code "163") (name "unconnected-(J4-Pad26)") (class "Default")
      (node (ref "J4") (pin "26") (pinfunction "26_26") (pintype "passive+no_connect"))
    )
    (net (code "164") (name "unconnected-(J4-Pad122)") (class "Default")
      (node (ref "J4") (pin "122") (pinfunction "122_122") (pintype "passive"))
    )
    (net (code "165") (name "unconnected-(J4-Pad123)") (class "Default")
      (node (ref "J4") (pin "123") (pinfunction "123_123") (pintype "passive"))
    )
    (net (code "166") (name "unconnected-(J4-Pad125)") (class "Default")
      (node (ref "J4") (pin "125") (pinfunction "125_125") (pintype "passive"))
    )
    (net (code "167") (name "unconnected-(J4-Pad126)") (class "Default")
      (node (ref "J4") (pin "126") (pinfunction "126_126") (pintype "passive"))
    )
    (net (code "168") (name "unconnected-(J4-Pad128)") (class "Default")
      (node (ref "J4") (pin "128") (pinfunction "128_128") (pintype "passive"))
    )
    (net (code "169") (name "unconnected-(J4-Pad129)") (class "Default")
      (node (ref "J4") (pin "129") (pinfunction "129_129") (pintype "passive"))
    )
    (net (code "170") (name "unconnected-(J4-Pad132)") (class "Default")
      (node (ref "J4") (pin "132") (pinfunction "132_132") (pintype "passive"))
    )
    (net (code "171") (name "unconnected-(J4-Pad133)") (class "Default")
      (node (ref "J4") (pin "133") (pinfunction "133_133") (pintype "passive"))
    )
    (net (code "172") (name "unconnected-(J4-Pad135)") (class "Default")
      (node (ref "J4") (pin "135") (pinfunction "135_135") (pintype "passive"))
    )
    (net (code "173") (name "unconnected-(J4-Pad136)") (class "Default")
      (node (ref "J4") (pin "136") (pinfunction "136_136") (pintype "passive"))
    )
    (net (code "174") (name "unconnected-(J4-Pad138)") (class "Default")
      (node (ref "J4") (pin "138") (pinfunction "138_138") (pintype "passive"))
    )
    (net (code "175") (name "unconnected-(J4-Pad139)") (class "Default")
      (node (ref "J4") (pin "139") (pinfunction "139_139") (pintype "passive"))
    )
    (net (code "176") (name "unconnected-(J4-Pad142)") (class "Default")
      (node (ref "J4") (pin "142") (pinfunction "142_142") (pintype "passive"))
    )
    (net (code "177") (name "unconnected-(J4-Pad143)") (class "Default")
      (node (ref "J4") (pin "143") (pinfunction "143_143") (pintype "passive"))
    )
    (net (code "178") (name "unconnected-(J4-Pad145)") (class "Default")
      (node (ref "J4") (pin "145") (pinfunction "145_145") (pintype "passive"))
    )
    (net (code "179") (name "unconnected-(J4-Pad146)") (class "Default")
      (node (ref "J4") (pin "146") (pinfunction "146_146") (pintype "passive"))
    )
    (net (code "180") (name "unconnected-(J4-Pad148)") (class "Default")
      (node (ref "J4") (pin "148") (pinfunction "148_148") (pintype "passive"))
    )
    (net (code "181") (name "unconnected-(J4-Pad149)") (class "Default")
      (node (ref "J4") (pin "149") (pinfunction "149_149") (pintype "passive"))
    )
    (net (code "182") (name "unconnected-(J4-Pad152)") (class "Default")
      (node (ref "J4") (pin "152") (pinfunction "152_152") (pintype "passive"))
    )
    (net (code "183") (name "unconnected-(J4-Pad153)") (class "Default")
      (node (ref "J4") (pin "153") (pinfunction "153_153") (pintype "passive"))
    )
    (net (code "184") (name "unconnected-(J4-Pad155)") (class "Default")
      (node (ref "J4") (pin "155") (pinfunction "155_155") (pintype "passive"))
    )
    (net (code "185") (name "unconnected-(J4-Pad156)") (class "Default")
      (node (ref "J4") (pin "156") (pinfunction "156_156") (pintype "passive"))
    )
    (net (code "186") (name "unconnected-(J4-Pad158)") (class "Default")
      (node (ref "J4") (pin "158") (pinfunction "158_158") (pintype "passive"))
    )
    (net (code "187") (name "unconnected-(J4-Pad159)") (class "Default")
      (node (ref "J4") (pin "159") (pinfunction "159_159") (pintype "passive"))
    )
    (net (code "188") (name "unconnected-(J4-Pad162)") (class "Default")
      (node (ref "J4") (pin "162") (pinfunction "162_162") (pintype "passive"))
    )
    (net (code "189") (name "unconnected-(J4-Pad163)") (class "Default")
      (node (ref "J4") (pin "163") (pinfunction "163_163") (pintype "passive"))
    )
    (net (code "190") (name "unconnected-(J4-Pad165)") (class "Default")
      (node (ref "J4") (pin "165") (pinfunction "165_165") (pintype "passive"))
    )
    (net (code "191") (name "unconnected-(J4-Pad166)") (class "Default")
      (node (ref "J4") (pin "166") (pinfunction "166_166") (pintype "passive"))
    )
    (net (code "192") (name "unconnected-(J4-Pad168)") (class "Default")
      (node (ref "J4") (pin "168") (pinfunction "168_168") (pintype "passive"))
    )
    (net (code "193") (name "unconnected-(J4-Pad169)") (class "Default")
      (node (ref "J4") (pin "169") (pinfunction "169_169") (pintype "passive"))
    )
    (net (code "194") (name "unconnected-(J4-Pad172)") (class "Default")
      (node (ref "J4") (pin "172") (pinfunction "172_172") (pintype "passive"))
    )
    (net (code "195") (name "unconnected-(J4-Pad173)") (class "Default")
      (node (ref "J4") (pin "173") (pinfunction "173_173") (pintype "passive"))
    )
    (net (code "196") (name "unconnected-(J4-Pad175)") (class "Default")
      (node (ref "J4") (pin "175") (pinfunction "175_175") (pintype "passive"))
    )
    (net (code "197") (name "unconnected-(J4-Pad176)") (class "Default")
      (node (ref "J4") (pin "176") (pinfunction "176_176") (pintype "passive"))
    )
    (net (code "198") (name "unconnected-(J4-Pad178)") (class "Default")
      (node (ref "J4") (pin "178") (pinfunction "178_178") (pintype "passive"))
    )
    (net (code "199") (name "unconnected-(J4-Pad179)") (class "Default")
      (node (ref "J4") (pin "179") (pinfunction "179_179") (pintype "passive"))
    )
    (net (code "200") (name "unconnected-(J4-Pad182)") (class "Default")
      (node (ref "J4") (pin "182") (pinfunction "182_182") (pintype "passive"))
    )
    (net (code "201") (name "unconnected-(J4-Pad183)") (class "Default")
      (node (ref "J4") (pin "183") (pinfunction "183_183") (pintype "passive"))
    )
    (net (code "202") (name "unconnected-(J4-Pad185)") (class "Default")
      (node (ref "J4") (pin "185") (pinfunction "185_185") (pintype "passive"))
    )
    (net (code "203") (name "unconnected-(J4-Pad186)") (class "Default")
      (node (ref "J4") (pin "186") (pinfunction "186_186") (pintype "passive"))
    )
    (net (code "204") (name "unconnected-(J4-Pad188)") (class "Default")
      (node (ref "J4") (pin "188") (pinfunction "188_188") (pintype "passive"))
    )
    (net (code "205") (name "unconnected-(J4-Pad189)") (class "Default")
      (node (ref "J4") (pin "189") (pinfunction "189_189") (pintype "passive"))
    )
    (net (code "206") (name "unconnected-(J4-Pad192)") (class "Default")
      (node (ref "J4") (pin "192") (pinfunction "192_192") (pintype "passive"))
    )
    (net (code "207") (name "unconnected-(J4-Pad193)") (class "Default")
      (node (ref "J4") (pin "193") (pinfunction "193_193") (pintype "passive"))
    )
    (net (code "208") (name "unconnected-(J4-Pad195)") (class "Default")
      (node (ref "J4") (pin "195") (pinfunction "195_195") (pintype "passive"))
    )
    (net (code "209") (name "unconnected-(J4-Pad196)") (class "Default")
      (node (ref "J4") (pin "196") (pinfunction "196_196") (pintype "passive"))
    )
    (net (code "210") (name "unconnected-(J4-Pad198)") (class "Default")
      (node (ref "J4") (pin "198") (pinfunction "198_198") (pintype "passive"))
    )
    (net (code "211") (name "unconnected-(J4-Pad199)") (class "Default")
      (node (ref "J4") (pin "199") (pinfunction "199_199") (pintype "passive"))
    )
    (net (code "212") (name "unconnected-(J4-Pad209)") (class "Default")
      (node (ref "J4") (pin "209") (pinfunction "209_209") (pintype "passive"))
    )
    (net (code "213") (name "unconnected-(J4-Pad306)") (class "Default")
      (node (ref "J4") (pin "306") (pinfunction "306_306") (pintype "passive"))
    )
  )
)
